# MCUDebug.net
KiCad netlist of a schematic drawn in Altium Designer
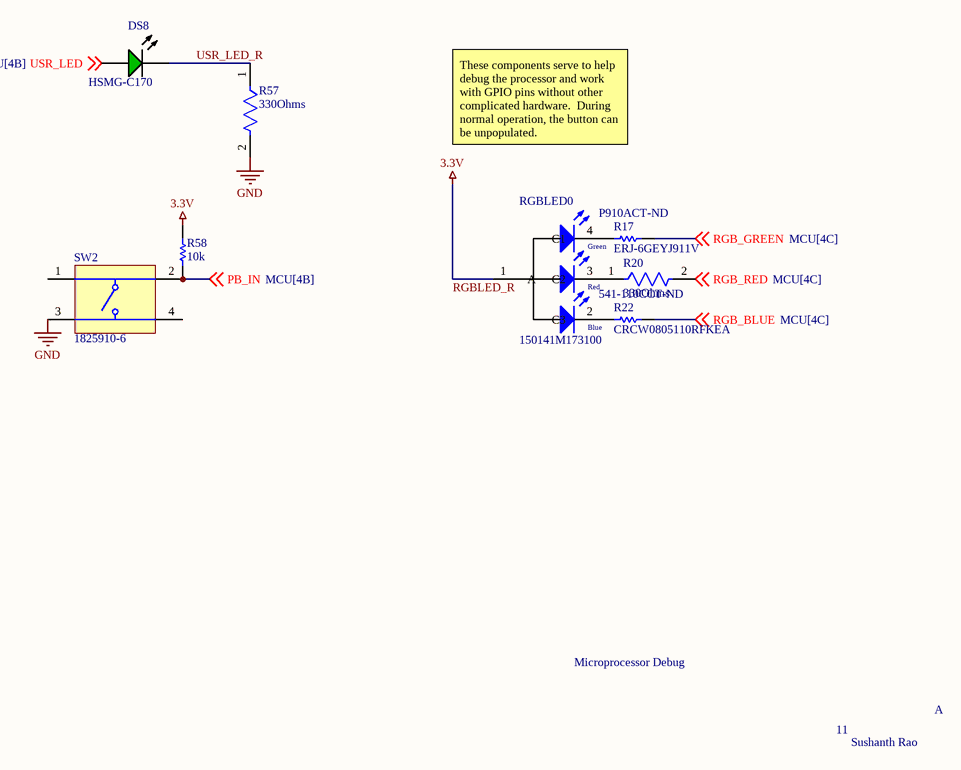
[diagram p0: MCUDebug.SchDoc]

(export (version "E")
  (design (tool "Eeschema 10.0.6"))
  (components
    (comp (ref "DS8")
      (value "HSMG-C170")
      (footprint "AVAG-HSMX-C170_V")
      (description "Chip LED, Green, 2.2 V, -40 to 85 degC, 2-Pin SMD, Pb-Free, Tape and Reel")
      (fields (field (name "MANUFACTURER") "Avago"))
      (libsource (lib "Altium Content Vault") (part "LED_GREEN_A1K2-2"))
    )
    (comp (ref "R17")
      (value "ERJ-6GEYJ911V")
      (footprint "RESC2013X70X40ML20T20")
      (fields
        (field (name "MANUFACTURER") "Panasonic")
        (field (name "SUPPLIER PART NUMBER 1") "P910ACT-ND")
        (field (name "TOLERANCE") "5%")
      )
      (libsource (lib "Altium Content Vault") (part "RES"))
    )
    (comp (ref "R20")
      (value "330Ohms")
      (footprint "FP-KTR10-IPC_C")
      (description "Res Thick Film 0805 300Ω 5% 0.125W ±200ppm/°C Automotive Paper T/R")
      (fields (field (name "TOLERANCE") "5%"))
      (libsource (lib "Altium Content Vault") (part "1029c3af85768c4190bb7ad29bc67b5"))
    )
    (comp (ref "R22")
      (value "CRCW0805110RFKEA")
      (footprint "RESC2013X50X30ML20T20")
      (fields
        (field (name "MANUFACTURER") "Vishay Dale")
        (field (name "SUPPLIER PART NUMBER 1") "541-110CCT-ND")
        (field (name "TOLERANCE") "1%")
      )
      (libsource (lib "Altium Content Vault") (part "RES"))
    )
    (comp (ref "R57")
      (value "330Ohms")
      (footprint "FP-KTR10-IPC_C")
      (description "Res Thick Film 0805 300Ω 5% 0.125W ±200ppm/°C Automotive Paper T/R")
      (fields (field (name "TOLERANCE") "5%"))
      (libsource (lib "Altium Content Vault") (part "1029c3af85768c4190bb7ad29bc67b5"))
    )
    (comp (ref "R58")
      (value "10k")
      (footprint "RESC2013X60X35NL10T20")
      (description "Chip Resistor, 10 KOhm, +/- 1%, 0.125 W, -55 to 155 degC, 0805 (2012 Metric), RoHS, Tape and Reel")
      (fields
        (field (name "MANUFACTURER") "Yageo")
        (field (name "MANUFACTURER PART NUMBER") "RC0805FR-0710KL")
      )
      (libsource (lib "Altium Content Vault") (part "RES-2"))
    )
    (comp (ref "RGBLED0")
      (value "150141M173100")
      (footprint "3528_A")
      (description "SMD Full-Color Top LED, WL-SFTW, Red & Green & Blue")
      (fields (field (name "MANUFACTURER") "Wuerth Elektronik"))
      (libsource (lib "Altium Content Vault") (part "WE-LED_RGB_A1B2R3G4-4"))
    )
    (comp (ref "SW2")
      (value "1825910-6")
      (footprint "TECO-1825910-6_V")
      (description "Tact Switch, SPST-NO, 0.05 A, -35 to 85 degC, 4-Pin THD, RoHS, Bulk")
      (fields (field (name "MANUFACTURER") "TE Connectivity"))
      (libsource (lib "Altium Content Vault") (part "SW-SPST-4_A"))
    )
  )
  (nets
    (net (code "1") (name "/USR_LED_R") (class "Default")
      (node (ref "DS8") (pin "2") (pinfunction "K_2") (pintype "passive"))
      (node (ref "R57") (pin "1") (pinfunction "1_1") (pintype "passive"))
    )
    (net (code "2") (name "3.3V") (class "Default")
      (node (ref "R58") (pin "2") (pinfunction "2_2") (pintype "passive"))
      (node (ref "RGBLED0") (pin "1") (pinfunction "A_1") (pintype "passive"))
    )
    (net (code "3") (name "GND") (class "Default")
      (node (ref "R57") (pin "2") (pinfunction "2_2") (pintype "passive"))
      (node (ref "SW2") (pin "3") (pinfunction "3_3") (pintype "passive"))
    )
    (net (code "4") (name "Net-(RGBLED0-C1)") (class "Default")
      (node (ref "R17") (pin "1") (pinfunction "1_1") (pintype "passive"))
      (node (ref "RGBLED0") (pin "4") (pinfunction "C1_4") (pintype "passive"))
    )
    (net (code "5") (name "Net-(RGBLED0-C2)") (class "Default")
      (node (ref "R20") (pin "1") (pinfunction "1_1") (pintype "passive"))
      (node (ref "RGBLED0") (pin "3") (pinfunction "C2_3") (pintype "passive"))
    )
    (net (code "6") (name "Net-(RGBLED0-C3)") (class "Default")
      (node (ref "R22") (pin "1") (pinfunction "1_1") (pintype "passive"))
      (node (ref "RGBLED0") (pin "2") (pinfunction "C3_2") (pintype "passive"))
    )
    (net (code "7") (name "PB_IN") (class "Default")
      (node (ref "R58") (pin "1") (pinfunction "1_1") (pintype "passive"))
      (node (ref "SW2") (pin "2") (pinfunction "2_2") (pintype "passive"))
    )
    (net (code "8") (name "RGB_BLUE") (class "Default")
      (node (ref "R22") (pin "2") (pinfunction "2_2") (pintype "passive"))
    )
    (net (code "9") (name "RGB_GREEN") (class "Default")
      (node (ref "R17") (pin "2") (pinfunction "2_2") (pintype "passive"))
    )
    (net (code "10") (name "RGB_RED") (class "Default")
      (node (ref "R20") (pin "2") (pinfunction "2_2") (pintype "passive"))
    )
    (net (code "11") (name "USR_LED") (class "Default")
      (node (ref "DS8") (pin "1") (pinfunction "A_1") (pintype "passive"))
    )
    (net (code "12") (name "unconnected-(SW2-Pad1)") (class "Default")
      (node (ref "SW2") (pin "1") (pinfunction "1_1") (pintype "passive"))
    )
    (net (code "13") (name "unconnected-(SW2-Pad4)") (class "Default")
      (node (ref "SW2") (pin "4") (pinfunction "4_4") (pintype "passive"))
    )
  )
)
